# SCH_555-Timer_2025-10-19_1.net
KiCad netlist of a schematic drawn in EasyEDA
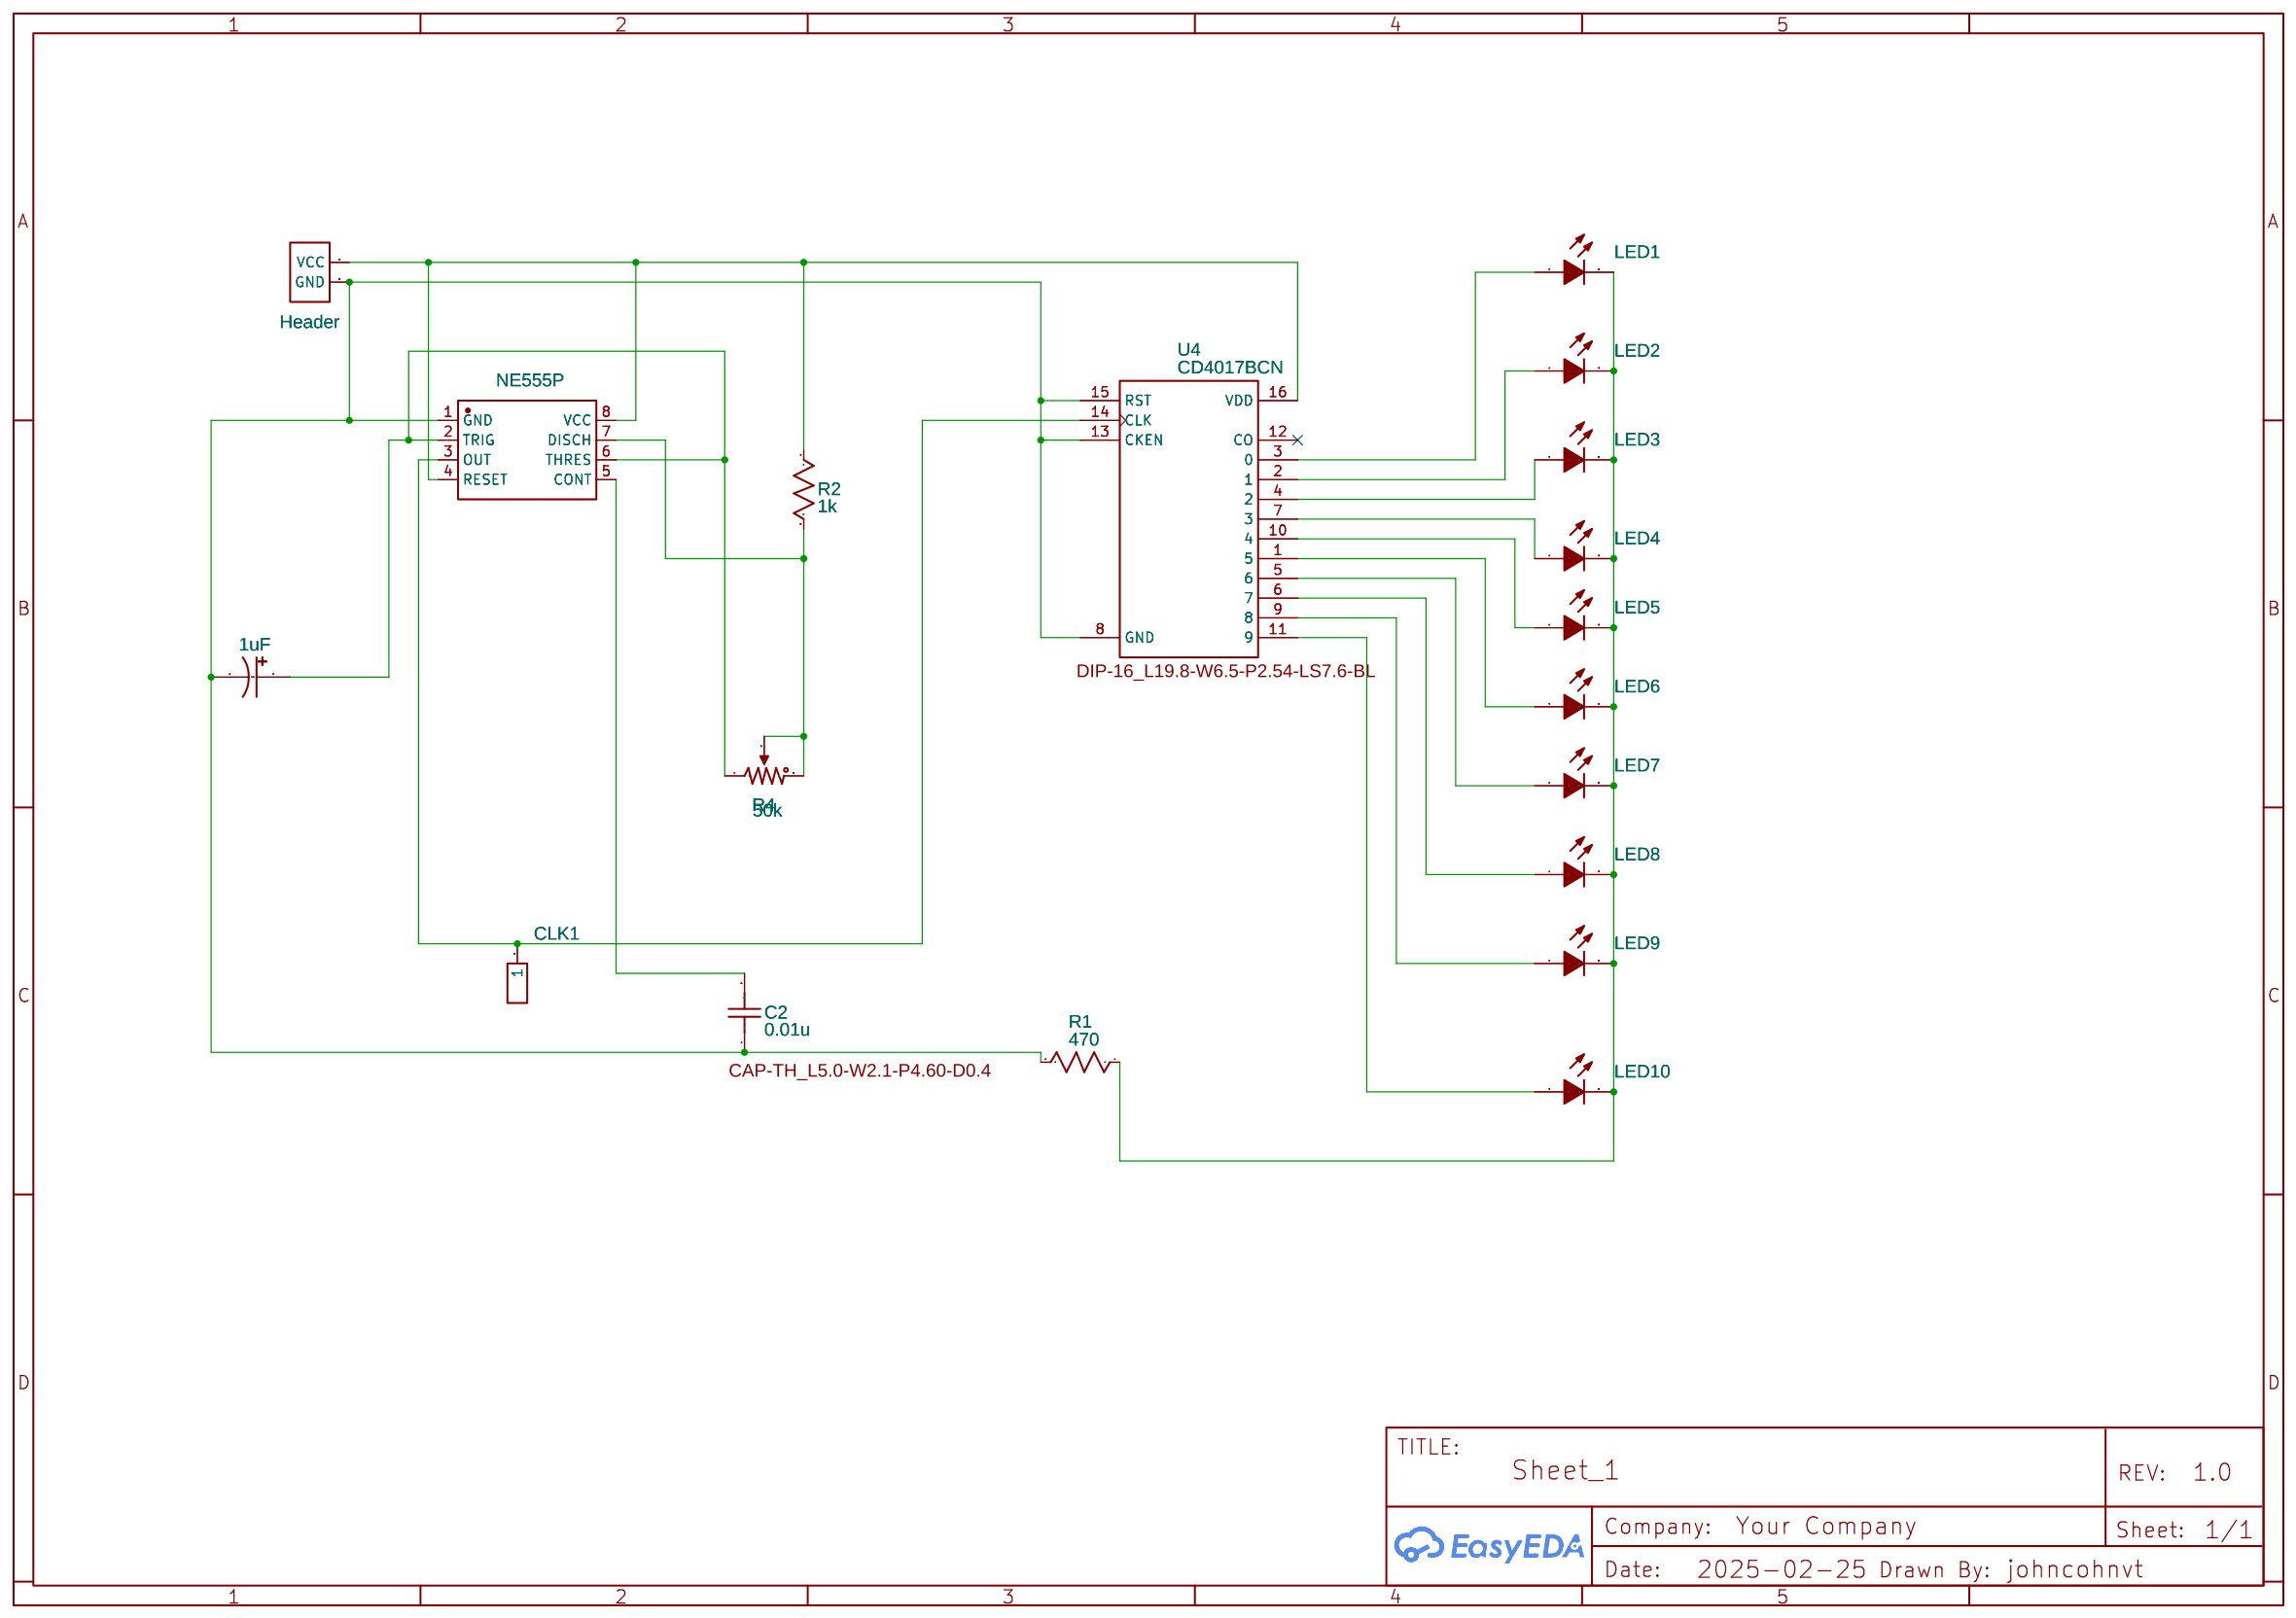
[diagram p0: schematic sheet]

(export (version "E")
  (design (tool "Eeschema 10.0.6"))
  (components
    (comp (ref "C1")
      (value "1uF")
      (fields (field (name "Manufacturer Part") "UVZ1H010MDD") (field (name "Manufacturer") "Nichicon(尼吉康)"))
      (libsource (lib "") (part "UVZ1H010MDD"))
    )
    (comp (ref "C2") (value "0.01u") (libsource (lib "") (part "C_0603_US")))
    (comp (ref "CLK1")
      (value "C81276")
      (fields
        (field (name "Manufacturer Part") "2.54-1*1P针")
        (field (name "Manufacturer") "BOOMELE(Boom Precision Elec)")
      )
      (libsource (lib "") (part "Header-Male-2.54_1x1"))
    )
    (comp (ref "H1") (value "Header") (libsource (lib "") (part "HEADER-FEMALE-2.54_1X2")))
    (comp (ref "LED1") (value "LED_5MM") (libsource (lib "") (part "LED_5MM")))
    (comp (ref "LED2") (value "LED_5MM") (libsource (lib "") (part "LED_5MM")))
    (comp (ref "LED3") (value "LED_5MM") (libsource (lib "") (part "LED_5MM")))
    (comp (ref "LED4") (value "LED_5MM") (libsource (lib "") (part "LED_5MM")))
    (comp (ref "LED5") (value "LED_5MM") (libsource (lib "") (part "LED_5MM")))
    (comp (ref "LED6") (value "LED_5MM") (libsource (lib "") (part "LED_5MM")))
    (comp (ref "LED7") (value "LED_5MM") (libsource (lib "") (part "LED_5MM")))
    (comp (ref "LED8") (value "LED_5MM") (libsource (lib "") (part "LED_5MM")))
    (comp (ref "LED9") (value "LED_5MM") (libsource (lib "") (part "LED_5MM")))
    (comp (ref "LED10") (value "LED_5MM") (libsource (lib "") (part "LED_5MM")))
    (comp (ref "R1")
      (value "470")
      (fields (field (name "Manufacturer Part") "?"))
      (libsource (lib "") (part "Resistor"))
    )
    (comp (ref "R2")
      (value "1k")
      (fields (field (name "Manufacturer Part") "?"))
      (libsource (lib "") (part "Resistor_1"))
    )
    (comp (ref "R4")
      (value "50k")
      (fields (field (name "Manufacturer Part") "?"))
      (libsource (lib "") (part "Potentiometer"))
    )
    (comp (ref "U2")
      (value "NE555P")
      (fields (field (name "Manufacturer") "TI(德州仪器)"))
      (libsource (lib "") (part "NE555P"))
    )
    (comp (ref "U4") (value "CD4017BCN") (libsource (lib "") (part "CD4017BCN")))
  )
  (nets
    (net (code "1") (name "Net-(H1-GND)") (class "Default")
      (node (ref "C1") (pin "2") (pinfunction "2_2") (pintype "unspecified"))
      (node (ref "C2") (pin "1") (pinfunction "1_1") (pintype "unspecified"))
      (node (ref "H1") (pin "2") (pinfunction "GND_2") (pintype "unspecified"))
      (node (ref "R1") (pin "2") (pinfunction "2_2") (pintype "unspecified"))
      (node (ref "U2") (pin "1") (pinfunction "GND_1") (pintype "unspecified"))
      (node (ref "U4") (pin "13") (pinfunction "CKEN_13") (pintype "unspecified"))
      (node (ref "U4") (pin "15") (pinfunction "RST_15") (pintype "unspecified"))
      (node (ref "U4") (pin "8") (pinfunction "GND_8") (pintype "passive"))
    )
    (net (code "2") (name "Net-(H1-VCC)") (class "Default")
      (node (ref "H1") (pin "1") (pinfunction "VCC_1") (pintype "unspecified"))
      (node (ref "R2") (pin "1") (pinfunction "1_1") (pintype "unspecified"))
      (node (ref "U2") (pin "4") (pinfunction "RESET_4") (pintype "unspecified"))
      (node (ref "U2") (pin "8") (pinfunction "VCC_8") (pintype "unspecified"))
      (node (ref "U4") (pin "16") (pinfunction "VDD_16") (pintype "passive"))
    )
    (net (code "3") (name "Net-(LED1-A)") (class "Default")
      (node (ref "LED1") (pin "1") (pinfunction "A_1") (pintype "input"))
      (node (ref "U4") (pin "3") (pinfunction "0_3") (pintype "output"))
    )
    (net (code "4") (name "Net-(LED1-K)") (class "Default")
      (node (ref "LED1") (pin "2") (pinfunction "K_2") (pintype "input"))
      (node (ref "LED10") (pin "2") (pinfunction "K_2") (pintype "input"))
      (node (ref "LED2") (pin "2") (pinfunction "K_2") (pintype "input"))
      (node (ref "LED3") (pin "2") (pinfunction "K_2") (pintype "input"))
      (node (ref "LED4") (pin "2") (pinfunction "K_2") (pintype "input"))
      (node (ref "LED5") (pin "2") (pinfunction "K_2") (pintype "input"))
      (node (ref "LED6") (pin "2") (pinfunction "K_2") (pintype "input"))
      (node (ref "LED7") (pin "2") (pinfunction "K_2") (pintype "input"))
      (node (ref "LED8") (pin "2") (pinfunction "K_2") (pintype "input"))
      (node (ref "LED9") (pin "2") (pinfunction "K_2") (pintype "input"))
      (node (ref "R1") (pin "1") (pinfunction "1_1") (pintype "unspecified"))
    )
    (net (code "5") (name "Net-(LED2-A)") (class "Default")
      (node (ref "LED2") (pin "1") (pinfunction "A_1") (pintype "input"))
      (node (ref "U4") (pin "2") (pinfunction "1_2") (pintype "output"))
    )
    (net (code "6") (name "Net-(LED3-A)") (class "Default")
      (node (ref "LED3") (pin "1") (pinfunction "A_1") (pintype "input"))
      (node (ref "U4") (pin "4") (pinfunction "2_4") (pintype "output"))
    )
    (net (code "7") (name "Net-(LED4-A)") (class "Default")
      (node (ref "LED4") (pin "1") (pinfunction "A_1") (pintype "input"))
      (node (ref "U4") (pin "7") (pinfunction "3_7") (pintype "output"))
    )
    (net (code "8") (name "Net-(LED5-A)") (class "Default")
      (node (ref "LED5") (pin "1") (pinfunction "A_1") (pintype "input"))
      (node (ref "U4") (pin "10") (pinfunction "4_10") (pintype "output"))
    )
    (net (code "9") (name "Net-(LED6-A)") (class "Default")
      (node (ref "LED6") (pin "1") (pinfunction "A_1") (pintype "input"))
      (node (ref "U4") (pin "1") (pinfunction "5_1") (pintype "output"))
    )
    (net (code "10") (name "Net-(LED7-A)") (class "Default")
      (node (ref "LED7") (pin "1") (pinfunction "A_1") (pintype "input"))
      (node (ref "U4") (pin "5") (pinfunction "6_5") (pintype "output"))
    )
    (net (code "11") (name "Net-(LED8-A)") (class "Default")
      (node (ref "LED8") (pin "1") (pinfunction "A_1") (pintype "input"))
      (node (ref "U4") (pin "6") (pinfunction "7_6") (pintype "output"))
    )
    (net (code "12") (name "Net-(LED9-A)") (class "Default")
      (node (ref "LED9") (pin "1") (pinfunction "A_1") (pintype "input"))
      (node (ref "U4") (pin "9") (pinfunction "8_9") (pintype "output"))
    )
    (net (code "13") (name "Net-(LED10-A)") (class "Default")
      (node (ref "LED10") (pin "1") (pinfunction "A_1") (pintype "input"))
      (node (ref "U4") (pin "11") (pinfunction "9_11") (pintype "output"))
    )
    (net (code "14") (name "Net-(R4-2)") (class "Default")
      (node (ref "R2") (pin "2") (pinfunction "2_2") (pintype "unspecified"))
      (node (ref "R4") (pin "2") (pinfunction "3_2") (pintype "unspecified"))
      (node (ref "R4") (pin "3") (pinfunction "2_3") (pintype "unspecified"))
      (node (ref "U2") (pin "7") (pinfunction "DISCH_7") (pintype "unspecified"))
    )
    (net (code "15") (name "Net-(U2-CONT)") (class "Default")
      (node (ref "C2") (pin "2") (pinfunction "2_2") (pintype "unspecified"))
      (node (ref "U2") (pin "5") (pinfunction "CONT_5") (pintype "unspecified"))
    )
    (net (code "16") (name "Net-(U2-OUT)") (class "Default")
      (node (ref "CLK1") (pin "1") (pinfunction "1_1") (pintype "unspecified"))
      (node (ref "U2") (pin "3") (pinfunction "OUT_3") (pintype "unspecified"))
      (node (ref "U4") (pin "14") (pinfunction "CLK_14") (pintype "unspecified"))
    )
    (net (code "17") (name "Net-(U2-THRES)") (class "Default")
      (node (ref "C1") (pin "1") (pinfunction "1_1") (pintype "unspecified"))
      (node (ref "R4") (pin "1") (pinfunction "1_1") (pintype "unspecified"))
      (node (ref "U2") (pin "2") (pinfunction "TRIG_2") (pintype "unspecified"))
      (node (ref "U2") (pin "6") (pinfunction "THRES_6") (pintype "unspecified"))
    )
    (net (code "18") (name "unconnected-(U4-CO-Pad12)") (class "Default")
      (node (ref "U4") (pin "12") (pinfunction "CO_12") (pintype "output+no_connect"))
    )
  )
)
